# flat.net
KiCad netlist of a schematic drawn in Altium Designer
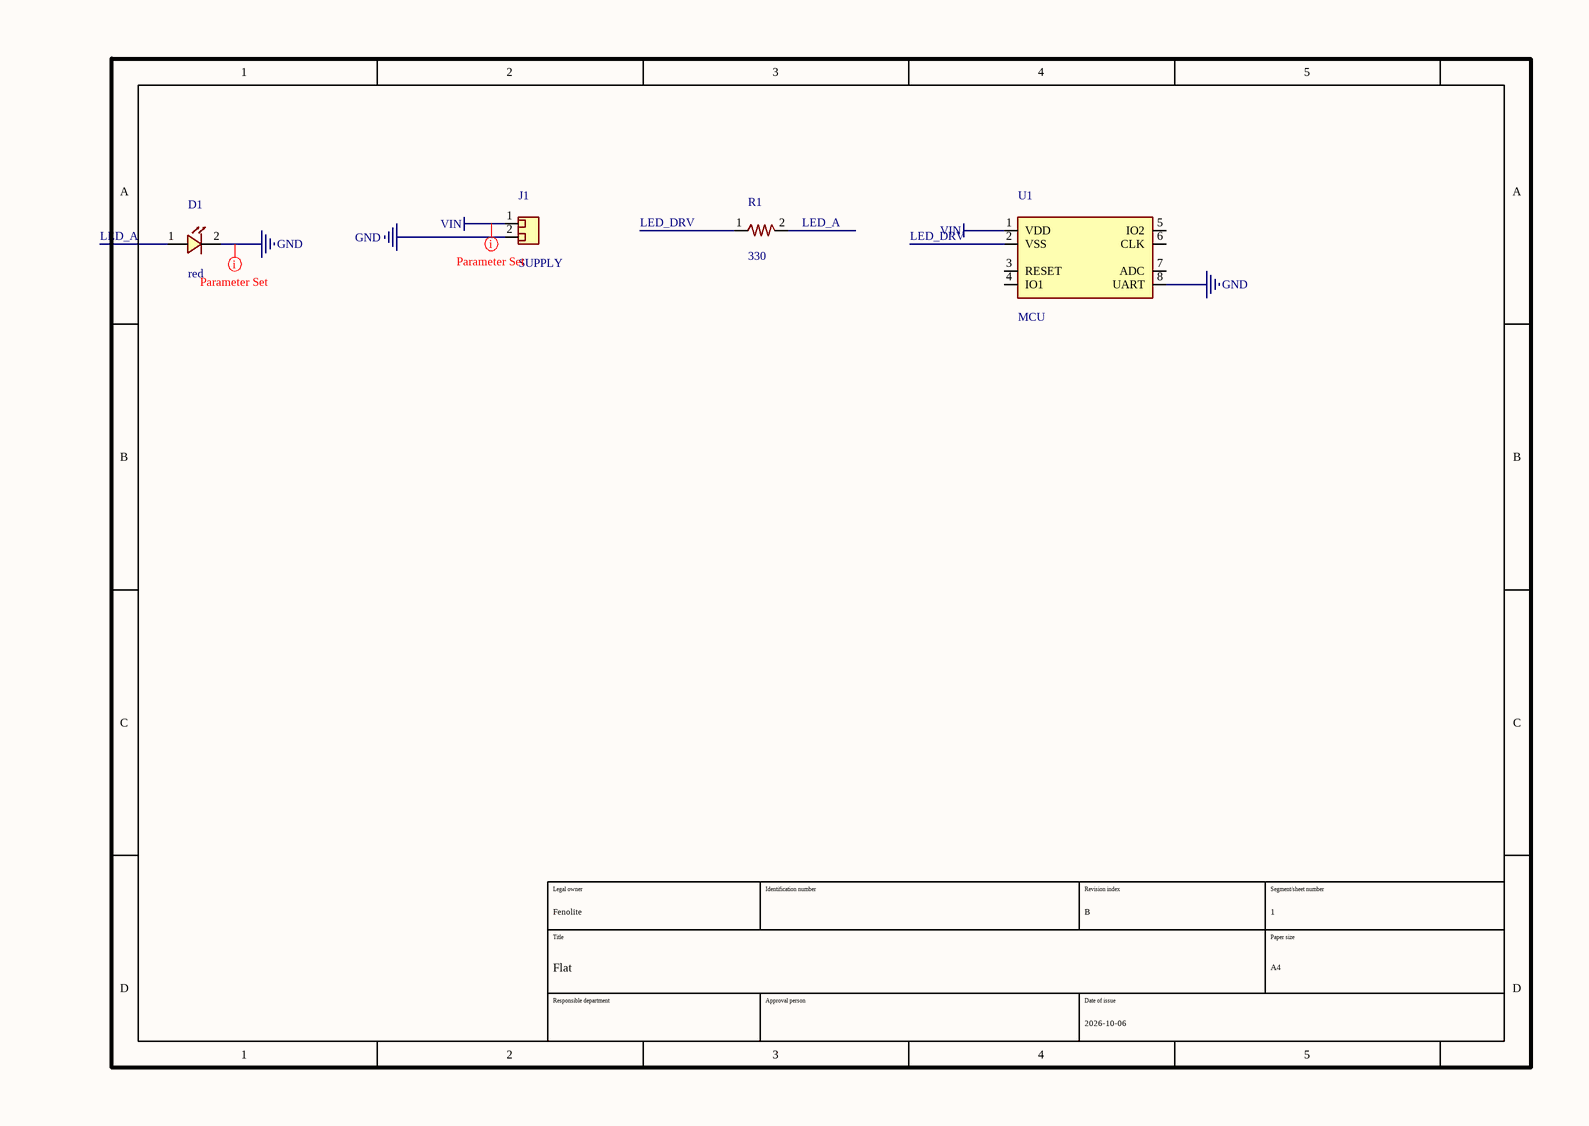
[diagram p0: flat.SchDoc]

(export (version "E")
  (design (tool "Eeschema 10.0.6"))
  (components
    (comp (ref "D1")
      (value "red")
      (footprint "flat:LED0603_Kingbright_APT1608SURCK")
      (libsource (lib "flat") (part "LED"))
    )
    (comp (ref "J1")
      (value "SUPPLY")
      (footprint "flat:Header_1x2_P2.54")
      (libsource (lib "flat") (part "Connector_2"))
    )
    (comp (ref "R1") (value "330") (footprint "flat:Chip_0603") (libsource (lib "flat") (part "Resistor")))
    (comp (ref "U1")
      (value "MCU")
      (footprint "flat:DIP8_Microchip_P")
      (libsource (lib "flat") (part "Microcontroller"))
    )
  )
  (nets
    (net (code "1") (name "/LED_A") (class "Default")
      (node (ref "D1") (pin "1") (pinfunction "A_1") (pintype "passive"))
      (node (ref "R1") (pin "2") (pinfunction "B_2") (pintype "passive"))
    )
    (net (code "2") (name "/LED_DRV") (class "Default")
      (node (ref "R1") (pin "1") (pinfunction "A_1") (pintype "passive"))
      (node (ref "U1") (pin "2") (pinfunction "VSS_2") (pintype "passive"))
    )
    (net (code "3") (name "GND") (class "Default")
      (node (ref "D1") (pin "2") (pinfunction "K_2") (pintype "passive"))
      (node (ref "J1") (pin "2") (pinfunction "Passive_2") (pintype "passive"))
      (node (ref "U1") (pin "8") (pinfunction "UART_8") (pintype "passive"))
    )
    (net (code "4") (name "VIN") (class "Default")
      (node (ref "J1") (pin "1") (pinfunction "Passive_1") (pintype "passive"))
      (node (ref "U1") (pin "1") (pinfunction "VDD_1") (pintype "passive"))
    )
    (net (code "5") (name "unconnected-(U1-ADC-Pad7)") (class "Default")
      (node (ref "U1") (pin "7") (pinfunction "ADC_7") (pintype "passive"))
    )
    (net (code "6") (name "unconnected-(U1-CLK-Pad6)") (class "Default")
      (node (ref "U1") (pin "6") (pinfunction "CLK_6") (pintype "passive"))
    )
    (net (code "7") (name "unconnected-(U1-IO1-Pad4)") (class "Default")
      (node (ref "U1") (pin "4") (pinfunction "IO1_4") (pintype "passive"))
    )
    (net (code "8") (name "unconnected-(U1-IO2-Pad5)") (class "Default")
      (node (ref "U1") (pin "5") (pinfunction "IO2_5") (pintype "passive"))
    )
    (net (code "9") (name "unconnected-(U1-RESET-Pad3)") (class "Default")
      (node (ref "U1") (pin "3") (pinfunction "RESET_3") (pintype "passive"))
    )
  )
)
